# void.net
KiCad netlist of a schematic drawn in EAGLE
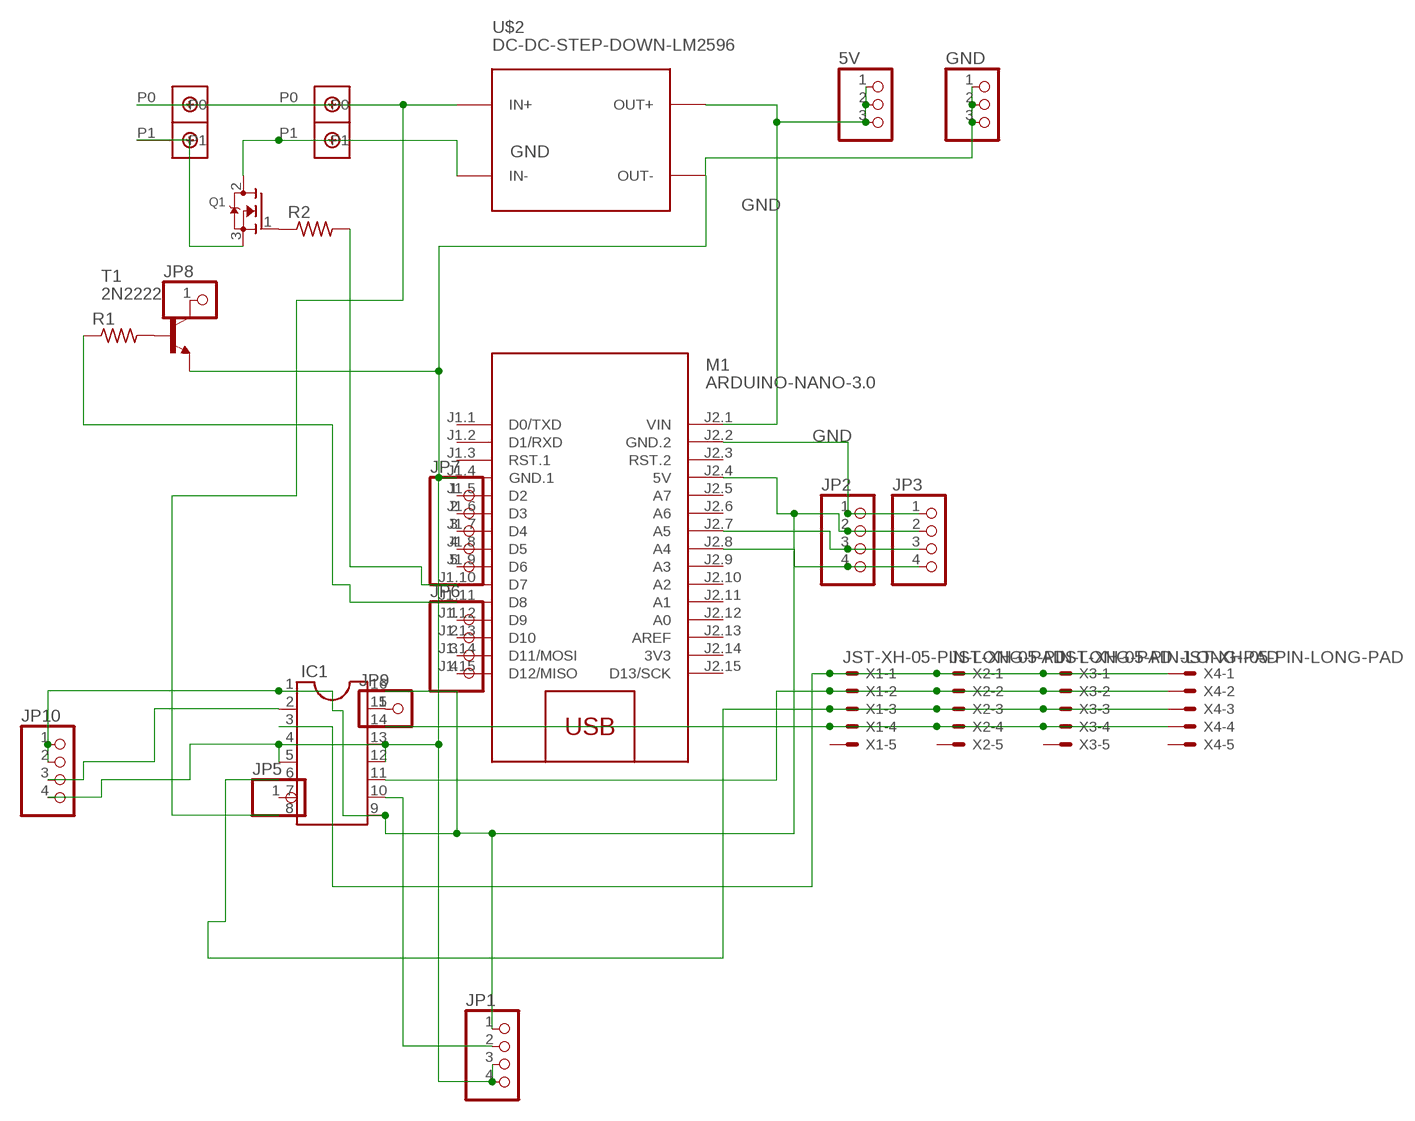
[diagram p0: schematic, sheet 1]

(export (version "E")
  (design (tool "Eeschema 10.0.6"))
  (components
    (comp (ref "5V")
      (value "PINHD-1X3")
      (footprint "eagle-import:1X03")
      (libsource (lib "eagle-import") (part "PINHD-1X3"))
    )
    (comp (ref "GND")
      (value "PINHD-1X3")
      (footprint "eagle-import:1X03")
      (libsource (lib "eagle-import") (part "PINHD-1X3"))
    )
    (comp (ref "IC1")
      (value "DIL16S")
      (footprint "eagle-import:SOCKET-16")
      (libsource (lib "eagle-import") (part "DIL16S"))
    )
    (comp (ref "JP1")
      (value "PINHD-1X4")
      (footprint "eagle-import:1X04")
      (libsource (lib "eagle-import") (part "PINHD-1X4"))
    )
    (comp (ref "JP2")
      (value "PINHD-1X4")
      (footprint "eagle-import:1X04")
      (libsource (lib "eagle-import") (part "PINHD-1X4"))
    )
    (comp (ref "JP3")
      (value "PINHD-1X4")
      (footprint "eagle-import:1X04")
      (libsource (lib "eagle-import") (part "PINHD-1X4"))
    )
    (comp (ref "JP5")
      (value "PINHD-1X1")
      (footprint "eagle-import:1X01")
      (libsource (lib "eagle-import") (part "PINHD-1X1"))
    )
    (comp (ref "JP6")
      (value "PINHD-1X4")
      (footprint "eagle-import:1X04")
      (libsource (lib "eagle-import") (part "PINHD-1X4"))
    )
    (comp (ref "JP7")
      (value "PINHD-1X5")
      (footprint "eagle-import:1X05")
      (libsource (lib "eagle-import") (part "PINHD-1X5"))
    )
    (comp (ref "JP8")
      (value "PINHD-1X1")
      (footprint "eagle-import:1X01")
      (libsource (lib "eagle-import") (part "PINHD-1X1"))
    )
    (comp (ref "JP9")
      (value "PINHD-1X1")
      (footprint "eagle-import:1X01")
      (libsource (lib "eagle-import") (part "PINHD-1X1"))
    )
    (comp (ref "JP10")
      (value "PINHD-1X4")
      (footprint "eagle-import:1X04")
      (libsource (lib "eagle-import") (part "PINHD-1X4"))
    )
    (comp (ref "M1")
      (value "ARDUINO-NANO-3.0")
      (footprint "eagle-import:ARDUINO-NANO-3.0")
      (libsource (lib "eagle-import") (part "ARDUINO-NANO-3.0"))
    )
    (comp (ref "POWER")
      (value "DBCONN-1X2")
      (footprint "eagle-import:DBCONN-1X2")
      (libsource (lib "eagle-import") (part "DBCONN-1X2"))
    )
    (comp (ref "PUMP")
      (value "DBCONN-1X2")
      (footprint "eagle-import:DBCONN-1X2")
      (libsource (lib "eagle-import") (part "DBCONN-1X2"))
    )
    (comp (ref "Q1")
      (value "MOSFET-NGDS_TO220V")
      (footprint "eagle-import:TO220V")
      (libsource (lib "eagle-import") (part "MOSFET-NGDS_TO220V"))
    )
    (comp (ref "R1")
      (value "R-US_0204/5")
      (footprint "eagle-import:0204_5")
      (libsource (lib "eagle-import") (part "R-US_0204/5"))
    )
    (comp (ref "R2")
      (value "R-US_0204/5")
      (footprint "eagle-import:0204_5")
      (libsource (lib "eagle-import") (part "R-US_0204/5"))
    )
    (comp (ref "T1")
      (value "2N2222")
      (footprint "eagle-import:TO92-EBC-OVAL")
      (libsource (lib "eagle-import") (part "2N2222"))
    )
    (comp (ref "U$2")
      (value "DC-DC-STEP-DOWN-LM2596")
      (footprint "eagle-import:DC-DC-STEP-DOWN-LM2596")
      (libsource (lib "eagle-import") (part "DC-DC-STEP-DOWN-LM2596"))
    )
    (comp (ref "X1")
      (value "JST-XH-05-PIN-LONG-PAD")
      (footprint "eagle-import:JST-XH-05-PACKAGE-LONG-PAD")
      (libsource (lib "eagle-import") (part "JST-XH-05-PIN-LONG-PAD"))
    )
    (comp (ref "X2")
      (value "JST-XH-05-PIN-LONG-PAD")
      (footprint "eagle-import:JST-XH-05-PACKAGE-LONG-PAD")
      (libsource (lib "eagle-import") (part "JST-XH-05-PIN-LONG-PAD"))
    )
    (comp (ref "X3")
      (value "JST-XH-05-PIN-LONG-PAD")
      (footprint "eagle-import:JST-XH-05-PACKAGE-LONG-PAD")
      (libsource (lib "eagle-import") (part "JST-XH-05-PIN-LONG-PAD"))
    )
    (comp (ref "X4")
      (value "JST-XH-05-PIN-LONG-PAD")
      (footprint "eagle-import:JST-XH-05-PACKAGE-LONG-PAD")
      (libsource (lib "eagle-import") (part "JST-XH-05-PIN-LONG-PAD"))
    )
  )
  (nets
    (net (code "1") (name "/3V3") (class "Default")
      (node (ref "M1") (pin "J2.14") (pinfunction "3V3_J2.14") (pintype "power_in"))
    )
    (net (code "2") (name "/GND") (class "Default")
      (node (ref "GND") (pin "1") (pinfunction "1_1") (pintype "passive"))
      (node (ref "GND") (pin "2") (pinfunction "2_2") (pintype "passive"))
      (node (ref "GND") (pin "3") (pinfunction "3_3") (pintype "passive"))
      (node (ref "IC1") (pin "12") (pinfunction "12_12") (pintype "passive"))
      (node (ref "IC1") (pin "13") (pinfunction "13_13") (pintype "passive"))
      (node (ref "IC1") (pin "4") (pinfunction "4_4") (pintype "passive"))
      (node (ref "IC1") (pin "5") (pinfunction "5_5") (pintype "passive"))
      (node (ref "JP1") (pin "3") (pinfunction "3_3") (pintype "passive"))
      (node (ref "JP1") (pin "4") (pinfunction "4_4") (pintype "passive"))
      (node (ref "JP10") (pin "4") (pinfunction "4_4") (pintype "passive"))
      (node (ref "JP2") (pin "1") (pinfunction "1_1") (pintype "passive"))
      (node (ref "JP3") (pin "1") (pinfunction "1_1") (pintype "passive"))
      (node (ref "M1") (pin "J1.4") (pinfunction "GND.1_J1.4") (pintype "power_in"))
      (node (ref "M1") (pin "J2.2") (pinfunction "GND.2_J2.2") (pintype "power_in"))
      (node (ref "POWER") (pin "P1") (pinfunction "P1_P1") (pintype "bidirectional"))
      (node (ref "Q1") (pin "2") (pinfunction "D_2") (pintype "bidirectional"))
      (node (ref "T1") (pin "E") (pinfunction "E_E") (pintype "passive"))
      (node (ref "U$2") (pin "IN-") (pinfunction "IN-_IN-") (pintype "bidirectional"))
      (node (ref "U$2") (pin "OUT-") (pinfunction "OUT-_OUT-") (pintype "bidirectional"))
    )
    (net (code "3") (name "Net-(IC1-Pad2)") (class "Default")
      (node (ref "IC1") (pin "2") (pinfunction "2_2") (pintype "passive"))
      (node (ref "JP10") (pin "3") (pinfunction "3_3") (pintype "passive"))
    )
    (net (code "4") (name "Net-(IC1-Pad7)") (class "Default")
      (node (ref "IC1") (pin "7") (pinfunction "7_7") (pintype "passive"))
      (node (ref "JP5") (pin "1") (pinfunction "1_1") (pintype "passive"))
    )
    (net (code "5") (name "Net-(IC1-Pad8)") (class "Default")
      (node (ref "IC1") (pin "8") (pinfunction "8_8") (pintype "passive"))
      (node (ref "POWER") (pin "P0") (pinfunction "P0_P0") (pintype "bidirectional"))
      (node (ref "PUMP") (pin "P0") (pinfunction "P0_P0") (pintype "bidirectional"))
      (node (ref "U$2") (pin "IN+") (pinfunction "IN+_IN+") (pintype "bidirectional"))
    )
    (net (code "6") (name "Net-(IC1-Pad10)") (class "Default")
      (node (ref "IC1") (pin "10") (pinfunction "10_10") (pintype "passive"))
      (node (ref "JP1") (pin "2") (pinfunction "2_2") (pintype "passive"))
    )
    (net (code "7") (name "Net-(IC1-Pad15)") (class "Default")
      (node (ref "IC1") (pin "15") (pinfunction "15_15") (pintype "passive"))
      (node (ref "JP9") (pin "1") (pinfunction "1_1") (pintype "passive"))
    )
    (net (code "8") (name "Net-(JP8-Pad1)") (class "Default")
      (node (ref "JP8") (pin "1") (pinfunction "1_1") (pintype "passive"))
      (node (ref "T1") (pin "C") (pinfunction "C_C") (pintype "passive"))
    )
    (net (code "9") (name "Net-(M1-5V)") (class "Default")
      (node (ref "IC1") (pin "1") (pinfunction "1_1") (pintype "passive"))
      (node (ref "IC1") (pin "16") (pinfunction "16_16") (pintype "passive"))
      (node (ref "IC1") (pin "9") (pinfunction "9_9") (pintype "passive"))
      (node (ref "JP1") (pin "1") (pinfunction "1_1") (pintype "passive"))
      (node (ref "JP10") (pin "1") (pinfunction "1_1") (pintype "passive"))
      (node (ref "JP10") (pin "2") (pinfunction "2_2") (pintype "passive"))
      (node (ref "JP2") (pin "2") (pinfunction "2_2") (pintype "passive"))
      (node (ref "JP3") (pin "2") (pinfunction "2_2") (pintype "passive"))
      (node (ref "M1") (pin "J2.4") (pinfunction "5V_J2.4") (pintype "power_in"))
    )
    (net (code "10") (name "Net-(M1-A4)") (class "Default")
      (node (ref "JP2") (pin "4") (pinfunction "4_4") (pintype "passive"))
      (node (ref "JP3") (pin "4") (pinfunction "4_4") (pintype "passive"))
      (node (ref "M1") (pin "J2.8") (pinfunction "A4_J2.8") (pintype "bidirectional"))
    )
    (net (code "11") (name "Net-(M1-A5)") (class "Default")
      (node (ref "JP2") (pin "3") (pinfunction "3_3") (pintype "passive"))
      (node (ref "JP3") (pin "3") (pinfunction "3_3") (pintype "passive"))
      (node (ref "M1") (pin "J2.7") (pinfunction "A5_J2.7") (pintype "bidirectional"))
    )
    (net (code "12") (name "Net-(M1-D2)") (class "Default")
      (node (ref "JP7") (pin "1") (pinfunction "1_1") (pintype "passive"))
      (node (ref "M1") (pin "J1.5") (pinfunction "D2_J1.5") (pintype "bidirectional"))
    )
    (net (code "13") (name "Net-(M1-D3)") (class "Default")
      (node (ref "JP7") (pin "2") (pinfunction "2_2") (pintype "passive"))
      (node (ref "M1") (pin "J1.6") (pinfunction "D3_J1.6") (pintype "bidirectional"))
    )
    (net (code "14") (name "Net-(M1-D4)") (class "Default")
      (node (ref "JP7") (pin "3") (pinfunction "3_3") (pintype "passive"))
      (node (ref "M1") (pin "J1.7") (pinfunction "D4_J1.7") (pintype "bidirectional"))
    )
    (net (code "15") (name "Net-(M1-D5)") (class "Default")
      (node (ref "JP7") (pin "4") (pinfunction "4_4") (pintype "passive"))
      (node (ref "M1") (pin "J1.8") (pinfunction "D5_J1.8") (pintype "bidirectional"))
    )
    (net (code "16") (name "Net-(M1-D6)") (class "Default")
      (node (ref "JP7") (pin "5") (pinfunction "5_5") (pintype "passive"))
      (node (ref "M1") (pin "J1.9") (pinfunction "D6_J1.9") (pintype "bidirectional"))
    )
    (net (code "17") (name "Net-(M1-D7)") (class "Default")
      (node (ref "M1") (pin "J1.10") (pinfunction "D7_J1.10") (pintype "bidirectional"))
      (node (ref "R2") (pin "2") (pinfunction "2_2") (pintype "passive"))
    )
    (net (code "18") (name "Net-(M1-D8)") (class "Default")
      (node (ref "M1") (pin "J1.11") (pinfunction "D8_J1.11") (pintype "bidirectional"))
      (node (ref "R1") (pin "1") (pinfunction "1_1") (pintype "passive"))
    )
    (net (code "19") (name "Net-(M1-D9)") (class "Default")
      (node (ref "JP6") (pin "1") (pinfunction "1_1") (pintype "passive"))
      (node (ref "M1") (pin "J1.12") (pinfunction "D9_J1.12") (pintype "bidirectional"))
    )
    (net (code "20") (name "Net-(M1-D10)") (class "Default")
      (node (ref "JP6") (pin "2") (pinfunction "2_2") (pintype "passive"))
      (node (ref "M1") (pin "J1.13") (pinfunction "D10_J1.13") (pintype "bidirectional"))
    )
    (net (code "21") (name "Net-(M1-D11{slash}MOSI)") (class "Default")
      (node (ref "JP6") (pin "3") (pinfunction "3_3") (pintype "passive"))
      (node (ref "M1") (pin "J1.14") (pinfunction "D11/MOSI_J1.14") (pintype "bidirectional"))
    )
    (net (code "22") (name "Net-(M1-D12{slash}MISO)") (class "Default")
      (node (ref "JP6") (pin "4") (pinfunction "4_4") (pintype "passive"))
      (node (ref "M1") (pin "J1.15") (pinfunction "D12/MISO_J1.15") (pintype "bidirectional"))
    )
    (net (code "23") (name "Net-(M1-VIN)") (class "Default")
      (node (ref "5V") (pin "1") (pinfunction "1_1") (pintype "passive"))
      (node (ref "5V") (pin "2") (pinfunction "2_2") (pintype "passive"))
      (node (ref "5V") (pin "3") (pinfunction "3_3") (pintype "passive"))
      (node (ref "M1") (pin "J2.1") (pinfunction "VIN_J2.1") (pintype "power_in"))
      (node (ref "U$2") (pin "OUT+") (pinfunction "OUT+_OUT+") (pintype "bidirectional"))
    )
    (net (code "24") (name "Net-(Q1-G)") (class "Default")
      (node (ref "Q1") (pin "1") (pinfunction "G_1") (pintype "bidirectional"))
      (node (ref "R2") (pin "1") (pinfunction "1_1") (pintype "passive"))
    )
    (net (code "25") (name "Net-(Q1-S)") (class "Default")
      (node (ref "PUMP") (pin "P1") (pinfunction "P1_P1") (pintype "bidirectional"))
      (node (ref "Q1") (pin "3") (pinfunction "S_3") (pintype "bidirectional"))
    )
    (net (code "26") (name "Net-(R1-Pad2)") (class "Default")
      (node (ref "R1") (pin "2") (pinfunction "2_2") (pintype "passive"))
      (node (ref "T1") (pin "B") (pinfunction "B_B") (pintype "passive"))
    )
    (net (code "27") (name "Net-(X1A-S)") (class "Default")
      (node (ref "IC1") (pin "3") (pinfunction "3_3") (pintype "passive"))
      (node (ref "X1") (pin "1") (pinfunction "S_1") (pintype "passive"))
      (node (ref "X2") (pin "1") (pinfunction "S_1") (pintype "passive"))
      (node (ref "X3") (pin "1") (pinfunction "S_1") (pintype "passive"))
      (node (ref "X4") (pin "1") (pinfunction "S_1") (pintype "passive"))
    )
    (net (code "28") (name "Net-(X1B-S)") (class "Default")
      (node (ref "IC1") (pin "11") (pinfunction "11_11") (pintype "passive"))
      (node (ref "X1") (pin "2") (pinfunction "S_2") (pintype "passive"))
      (node (ref "X2") (pin "2") (pinfunction "S_2") (pintype "passive"))
      (node (ref "X3") (pin "2") (pinfunction "S_2") (pintype "passive"))
      (node (ref "X4") (pin "2") (pinfunction "S_2") (pintype "passive"))
    )
    (net (code "29") (name "Net-(X1C-S)") (class "Default")
      (node (ref "IC1") (pin "6") (pinfunction "6_6") (pintype "passive"))
      (node (ref "X1") (pin "3") (pinfunction "S_3") (pintype "passive"))
      (node (ref "X2") (pin "3") (pinfunction "S_3") (pintype "passive"))
      (node (ref "X3") (pin "3") (pinfunction "S_3") (pintype "passive"))
      (node (ref "X4") (pin "3") (pinfunction "S_3") (pintype "passive"))
    )
    (net (code "30") (name "Net-(X1D-S)") (class "Default")
      (node (ref "IC1") (pin "14") (pinfunction "14_14") (pintype "passive"))
      (node (ref "X1") (pin "4") (pinfunction "S_4") (pintype "passive"))
      (node (ref "X2") (pin "4") (pinfunction "S_4") (pintype "passive"))
      (node (ref "X3") (pin "4") (pinfunction "S_4") (pintype "passive"))
      (node (ref "X4") (pin "4") (pinfunction "S_4") (pintype "passive"))
    )
    (net (code "31") (name "unconnected-(M1-A0-PadJ2.12)") (class "Default")
      (node (ref "M1") (pin "J2.12") (pinfunction "A0_J2.12") (pintype "bidirectional"))
    )
    (net (code "32") (name "unconnected-(M1-A1-PadJ2.11)") (class "Default")
      (node (ref "M1") (pin "J2.11") (pinfunction "A1_J2.11") (pintype "bidirectional"))
    )
    (net (code "33") (name "unconnected-(M1-A2-PadJ2.10)") (class "Default")
      (node (ref "M1") (pin "J2.10") (pinfunction "A2_J2.10") (pintype "bidirectional"))
    )
    (net (code "34") (name "unconnected-(M1-A3-PadJ2.9)") (class "Default")
      (node (ref "M1") (pin "J2.9") (pinfunction "A3_J2.9") (pintype "bidirectional"))
    )
    (net (code "35") (name "unconnected-(M1-A6-PadJ2.6)") (class "Default")
      (node (ref "M1") (pin "J2.6") (pinfunction "A6_J2.6") (pintype "bidirectional"))
    )
    (net (code "36") (name "unconnected-(M1-A7-PadJ2.5)") (class "Default")
      (node (ref "M1") (pin "J2.5") (pinfunction "A7_J2.5") (pintype "bidirectional"))
    )
    (net (code "37") (name "unconnected-(M1-AREF-PadJ2.13)") (class "Default")
      (node (ref "M1") (pin "J2.13") (pinfunction "AREF_J2.13") (pintype "bidirectional"))
    )
    (net (code "38") (name "unconnected-(M1-D0{slash}TXD-PadJ1.1)") (class "Default")
      (node (ref "M1") (pin "J1.1") (pinfunction "D0/TXD_J1.1") (pintype "bidirectional"))
    )
    (net (code "39") (name "unconnected-(M1-D1{slash}RXD-PadJ1.2)") (class "Default")
      (node (ref "M1") (pin "J1.2") (pinfunction "D1/RXD_J1.2") (pintype "bidirectional"))
    )
    (net (code "40") (name "unconnected-(M1-D13{slash}SCK-PadJ2.15)") (class "Default")
      (node (ref "M1") (pin "J2.15") (pinfunction "D13/SCK_J2.15") (pintype "bidirectional"))
    )
    (net (code "41") (name "unconnected-(M1-RST.1-PadJ1.3)") (class "Default")
      (node (ref "M1") (pin "J1.3") (pinfunction "RST.1_J1.3") (pintype "bidirectional"))
    )
    (net (code "42") (name "unconnected-(M1-RST.2-PadJ2.3)") (class "Default")
      (node (ref "M1") (pin "J2.3") (pinfunction "RST.2_J2.3") (pintype "bidirectional"))
    )
    (net (code "43") (name "unconnected-(X1E-S-Pad5)") (class "Default")
      (node (ref "X1") (pin "5") (pinfunction "S_5") (pintype "passive"))
    )
    (net (code "44") (name "unconnected-(X2E-S-Pad5)") (class "Default")
      (node (ref "X2") (pin "5") (pinfunction "S_5") (pintype "passive"))
    )
    (net (code "45") (name "unconnected-(X3E-S-Pad5)") (class "Default")
      (node (ref "X3") (pin "5") (pinfunction "S_5") (pintype "passive"))
    )
    (net (code "46") (name "unconnected-(X4E-S-Pad5)") (class "Default")
      (node (ref "X4") (pin "5") (pinfunction "S_5") (pintype "passive"))
    )
  )
)
